# lumiled_driver_ser.net
KiCad netlist of a schematic drawn in EAGLE
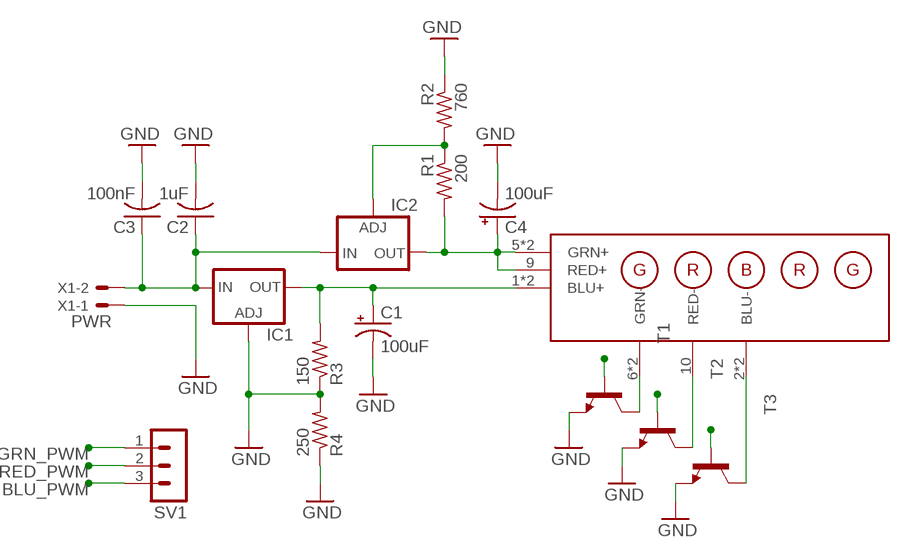
[diagram p0: schematic, sheet 1]

(export (version "E")
  (design (tool "Eeschema 10.0.6"))
  (components
    (comp (ref "C1")
      (value "100uF")
      (footprint "eagle-import:E2-5")
      (libsource (lib "eagle-import") (part "CPOL-USE2-5"))
    )
    (comp (ref "C2")
      (value "1uF")
      (footprint "eagle-import:C025-024X044")
      (libsource (lib "eagle-import") (part "C-US025-024X044"))
    )
    (comp (ref "C3")
      (value "100nF")
      (footprint "eagle-import:C025-024X044")
      (libsource (lib "eagle-import") (part "C-US025-024X044"))
    )
    (comp (ref "C4")
      (value "100uF")
      (footprint "eagle-import:E2-5")
      (libsource (lib "eagle-import") (part "CPOL-USE2-5"))
    )
    (comp (ref "IC1")
      (value "LM317TL")
      (footprint "eagle-import:317TL")
      (libsource (lib "eagle-import") (part "LM317TL"))
    )
    (comp (ref "IC2")
      (value "LM317TL")
      (footprint "eagle-import:317TL")
      (libsource (lib "eagle-import") (part "LM317TL"))
    )
    (comp (ref "R1")
      (value "200")
      (footprint "eagle-import:0309_12")
      (libsource (lib "eagle-import") (part "R-US_0309/12"))
    )
    (comp (ref "R2")
      (value "760")
      (footprint "eagle-import:0309_12")
      (libsource (lib "eagle-import") (part "R-US_0309/12"))
    )
    (comp (ref "R3")
      (value "150")
      (footprint "eagle-import:0309_12")
      (libsource (lib "eagle-import") (part "R-US_0309/12"))
    )
    (comp (ref "R4")
      (value "250")
      (footprint "eagle-import:0309_12")
      (libsource (lib "eagle-import") (part "R-US_0309/12"))
    )
    (comp (ref "SV1")
      (value "MA03-1")
      (footprint "eagle-import:MA03-1")
      (libsource (lib "eagle-import") (part "MA03-1"))
    )
    (comp (ref "T1")
      (value "-NPN-TO92")
      (footprint "eagle-import:TO92")
      (libsource (lib "eagle-import") (part "-NPN-TO92"))
    )
    (comp (ref "T2")
      (value "-NPN-TO92")
      (footprint "eagle-import:TO92")
      (libsource (lib "eagle-import") (part "-NPN-TO92"))
    )
    (comp (ref "T3")
      (value "-NPN-TO92")
      (footprint "eagle-import:TO92")
      (libsource (lib "eagle-import") (part "-NPN-TO92"))
    )
    (comp (ref "U$1")
      (value "LUMILED_5LED")
      (footprint "eagle-import:MA05-2")
      (libsource (lib "eagle-import") (part "LUMILED_5LED"))
    )
    (comp (ref "X1")
      (value "PWR")
      (footprint "eagle-import:22-23-2021")
      (fields (field (name "MF") "MOLEX") (field (name "MPN") "22-23-2021"))
      (libsource (lib "eagle-import") (part "22-23-2021"))
    )
  )
  (nets
    (net (code "1") (name "/BLU_PWM") (class "Default")
      (node (ref "SV1") (pin "3") (pinfunction "3_3") (pintype "passive"))
      (node (ref "T3") (pin "2") (pinfunction "B_2") (pintype "passive"))
    )
    (net (code "2") (name "/GRN_PWM") (class "Default")
      (node (ref "SV1") (pin "1") (pinfunction "1_1") (pintype "passive"))
      (node (ref "T1") (pin "2") (pinfunction "B_2") (pintype "passive"))
    )
    (net (code "3") (name "/RED_PWM") (class "Default")
      (node (ref "SV1") (pin "2") (pinfunction "2_2") (pintype "passive"))
      (node (ref "T2") (pin "2") (pinfunction "B_2") (pintype "passive"))
    )
    (net (code "4") (name "GND") (class "Default")
      (node (ref "C1") (pin "-") (pinfunction "-_-") (pintype "passive"))
      (node (ref "C2") (pin "2") (pinfunction "2_2") (pintype "passive"))
      (node (ref "C3") (pin "2") (pinfunction "2_2") (pintype "passive"))
      (node (ref "C4") (pin "-") (pinfunction "-_-") (pintype "passive"))
      (node (ref "IC1") (pin "1") (pinfunction "ADJ_1") (pintype "input"))
      (node (ref "R2") (pin "1") (pinfunction "1_1") (pintype "passive"))
      (node (ref "R3") (pin "1") (pinfunction "1_1") (pintype "passive"))
      (node (ref "R4") (pin "1") (pinfunction "1_1") (pintype "passive"))
      (node (ref "R4") (pin "2") (pinfunction "2_2") (pintype "passive"))
      (node (ref "T1") (pin "1") (pinfunction "E_1") (pintype "passive"))
      (node (ref "T2") (pin "1") (pinfunction "E_1") (pintype "passive"))
      (node (ref "T3") (pin "1") (pinfunction "E_1") (pintype "passive"))
      (node (ref "X1") (pin "1") (pinfunction "S_1") (pintype "passive"))
    )
    (net (code "5") (name "Net-(IC1-IN)") (class "Default")
      (node (ref "C2") (pin "1") (pinfunction "1_1") (pintype "passive"))
      (node (ref "C3") (pin "1") (pinfunction "1_1") (pintype "passive"))
      (node (ref "IC1") (pin "3") (pinfunction "IN_3") (pintype "input"))
      (node (ref "IC2") (pin "3") (pinfunction "IN_3") (pintype "input"))
      (node (ref "X1") (pin "2") (pinfunction "S_2") (pintype "passive"))
    )
    (net (code "6") (name "Net-(IC1-OUT)") (class "Default")
      (node (ref "C1") (pin "+") (pinfunction "+_+") (pintype "passive"))
      (node (ref "IC1") (pin "2") (pinfunction "OUT_2") (pintype "passive"))
      (node (ref "R3") (pin "2") (pinfunction "2_2") (pintype "passive"))
      (node (ref "U$1") (pin "1") (pinfunction "BLU+_1") (pintype "bidirectional"))
      (node (ref "U$1") (pin "3") (pinfunction "BLU+_3") (pintype "bidirectional"))
    )
    (net (code "7") (name "Net-(IC2-ADJ)") (class "Default")
      (node (ref "IC2") (pin "1") (pinfunction "ADJ_1") (pintype "input"))
      (node (ref "R1") (pin "1") (pinfunction "1_1") (pintype "passive"))
      (node (ref "R2") (pin "2") (pinfunction "2_2") (pintype "passive"))
    )
    (net (code "8") (name "Net-(IC2-OUT)") (class "Default")
      (node (ref "C4") (pin "+") (pinfunction "+_+") (pintype "passive"))
      (node (ref "IC2") (pin "2") (pinfunction "OUT_2") (pintype "passive"))
      (node (ref "R1") (pin "2") (pinfunction "2_2") (pintype "passive"))
      (node (ref "U$1") (pin "5") (pinfunction "GRN+_5") (pintype "bidirectional"))
      (node (ref "U$1") (pin "7") (pinfunction "GRN+_7") (pintype "bidirectional"))
      (node (ref "U$1") (pin "9") (pinfunction "RED+_9") (pintype "bidirectional"))
    )
    (net (code "9") (name "Net-(T1-C)") (class "Default")
      (node (ref "T1") (pin "3") (pinfunction "C_3") (pintype "passive"))
      (node (ref "U$1") (pin "6") (pinfunction "GRN-_6") (pintype "bidirectional"))
      (node (ref "U$1") (pin "8") (pinfunction "GRN-_8") (pintype "bidirectional"))
    )
    (net (code "10") (name "Net-(T2-C)") (class "Default")
      (node (ref "T2") (pin "3") (pinfunction "C_3") (pintype "passive"))
      (node (ref "U$1") (pin "10") (pinfunction "RED-_10") (pintype "bidirectional"))
    )
    (net (code "11") (name "Net-(T3-C)") (class "Default")
      (node (ref "T3") (pin "3") (pinfunction "C_3") (pintype "passive"))
      (node (ref "U$1") (pin "2") (pinfunction "BLU-_2") (pintype "bidirectional"))
      (node (ref "U$1") (pin "4") (pinfunction "BLU-_4") (pintype "bidirectional"))
    )
  )
)
